# FM-VHF-Oscillator.net
KiCad netlist of a schematic drawn in EAGLE
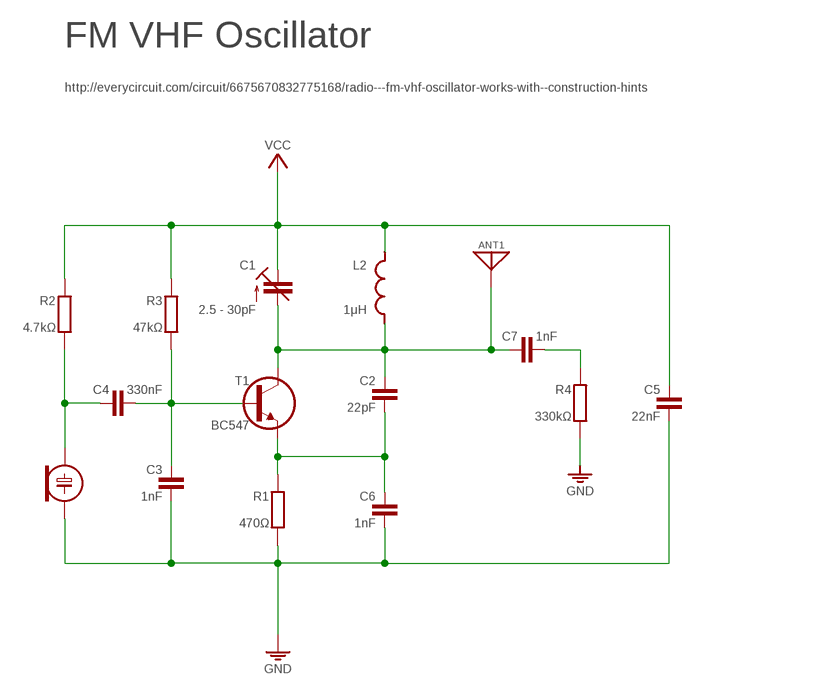
[diagram p0: schematic, sheet 1]

(export (version "E")
  (design (tool "Eeschema 10.0.6"))
  (components
    (comp (ref "ANT1")
      (value "ANT")
      (footprint "eagle-import:SPAD")
      (libsource (lib "eagle-import") (part "ANT"))
    )
    (comp (ref "C1")
      (value "2.5 - 30pF")
      (footprint "eagle-import:TRIM-2222-808")
      (libsource (lib "eagle-import") (part "C-TR-PH201272222-808-2PINB"))
    )
    (comp (ref "C2")
      (value "22pF")
      (footprint "eagle-import:C025-015X024")
      (libsource (lib "eagle-import") (part "C025-015X024"))
    )
    (comp (ref "C3")
      (value "1nF")
      (footprint "eagle-import:C050-020X036_V")
      (libsource (lib "eagle-import") (part "C050-020X036/V"))
    )
    (comp (ref "C4")
      (value "330nF")
      (footprint "eagle-import:C050-024X044")
      (libsource (lib "eagle-import") (part "C-H050-024X044"))
    )
    (comp (ref "C5")
      (value "22nF")
      (footprint "eagle-import:C050-020X044_V")
      (libsource (lib "eagle-import") (part "C050-020X044/V"))
    )
    (comp (ref "C6")
      (value "1nF")
      (footprint "eagle-import:C050-020X036")
      (libsource (lib "eagle-import") (part "C050-020X036"))
    )
    (comp (ref "C7")
      (value "1nF")
      (footprint "eagle-import:C050-024X044")
      (libsource (lib "eagle-import") (part "C-H050-024X044"))
    )
    (comp (ref "ECM")
      (value "ECM-4")
      (footprint "eagle-import:ECM-4")
      (libsource (lib "eagle-import") (part "ECM-4"))
    )
    (comp (ref "L2")
      (value "1μH")
      (footprint "eagle-import:L-04_7V-X")
      (libsource (lib "eagle-import") (part "L-SHORT04/7V-X"))
    )
    (comp (ref "R1")
      (value "470Ω")
      (footprint "eagle-import:0204_2V")
      (libsource (lib "eagle-import") (part "R0204/2V"))
    )
    (comp (ref "R2")
      (value "4.7kΩ")
      (footprint "eagle-import:0202_7-V")
      (libsource (lib "eagle-import") (part "R0202/7-V"))
    )
    (comp (ref "R3")
      (value "47kΩ")
      (footprint "eagle-import:0202_7-V")
      (libsource (lib "eagle-import") (part "R0202/7-V"))
    )
    (comp (ref "R4")
      (value "330kΩ")
      (footprint "eagle-import:0202_5-V")
      (libsource (lib "eagle-import") (part "R0202/5-V"))
    )
    (comp (ref "S2")
      (value "VCC_GNDPWR-R")
      (footprint "eagle-import:PWR-R")
      (libsource (lib "eagle-import") (part "VCC_GNDPWR-R"))
    )
    (comp (ref "T1")
      (value "BC547")
      (footprint "eagle-import:TO92-CBE")
      (libsource (lib "eagle-import") (part "BC547CBE"))
    )
  )
  (nets
    (net (code "1") (name "GND") (class "Default")
      (node (ref "C3") (pin "2") (pinfunction "2_2") (pintype "passive"))
      (node (ref "C5") (pin "2") (pinfunction "2_2") (pintype "passive"))
      (node (ref "C6") (pin "2") (pinfunction "2_2") (pintype "passive"))
      (node (ref "ECM") (pin "2") (pinfunction "-_2") (pintype "passive"))
      (node (ref "R1") (pin "2") (pinfunction "2_2") (pintype "passive"))
      (node (ref "R4") (pin "2") (pinfunction "2_2") (pintype "passive"))
      (node (ref "S2") (pin "1") (pinfunction "GND_1") (pintype "power_in"))
    )
    (net (code "2") (name "Net-(C1-A)") (class "Default")
      (node (ref "ANT1") (pin "1") (pinfunction "1_1") (pintype "output"))
      (node (ref "C1") (pin "2") (pinfunction "A_2") (pintype "passive"))
      (node (ref "C2") (pin "1") (pinfunction "1_1") (pintype "passive"))
      (node (ref "C7") (pin "1") (pinfunction "1_1") (pintype "passive"))
      (node (ref "L2") (pin "1") (pinfunction "1_1") (pintype "passive"))
      (node (ref "T1") (pin "C") (pinfunction "C_C") (pintype "passive"))
    )
    (net (code "3") (name "Net-(C1-E)") (class "Default")
      (node (ref "C1") (pin "3") (pinfunction "E_3") (pintype "passive"))
      (node (ref "C5") (pin "1") (pinfunction "1_1") (pintype "passive"))
      (node (ref "L2") (pin "2") (pinfunction "2_2") (pintype "passive"))
      (node (ref "R2") (pin "1") (pinfunction "1_1") (pintype "passive"))
      (node (ref "R3") (pin "1") (pinfunction "1_1") (pintype "passive"))
      (node (ref "S2") (pin "2") (pinfunction "VCC_2") (pintype "power_in"))
    )
    (net (code "4") (name "Net-(C2-Pad2)") (class "Default")
      (node (ref "C2") (pin "2") (pinfunction "2_2") (pintype "passive"))
      (node (ref "C6") (pin "1") (pinfunction "1_1") (pintype "passive"))
      (node (ref "R1") (pin "1") (pinfunction "1_1") (pintype "passive"))
      (node (ref "T1") (pin "E") (pinfunction "E_E") (pintype "passive"))
    )
    (net (code "5") (name "Net-(C3-Pad1)") (class "Default")
      (node (ref "C3") (pin "1") (pinfunction "1_1") (pintype "passive"))
      (node (ref "C4") (pin "2") (pinfunction "2_2") (pintype "passive"))
      (node (ref "R3") (pin "2") (pinfunction "2_2") (pintype "passive"))
      (node (ref "T1") (pin "B") (pinfunction "B_B") (pintype "passive"))
    )
    (net (code "6") (name "Net-(C7-Pad2)") (class "Default")
      (node (ref "C7") (pin "2") (pinfunction "2_2") (pintype "passive"))
      (node (ref "R4") (pin "1") (pinfunction "1_1") (pintype "passive"))
    )
    (net (code "7") (name "Net-(ECM-+)") (class "Default")
      (node (ref "C4") (pin "1") (pinfunction "1_1") (pintype "passive"))
      (node (ref "ECM") (pin "1") (pinfunction "+_1") (pintype "passive"))
      (node (ref "R2") (pin "2") (pinfunction "2_2") (pintype "passive"))
    )
  )
)
